# blinkm_mk2j.net
KiCad netlist of a schematic drawn in EAGLE
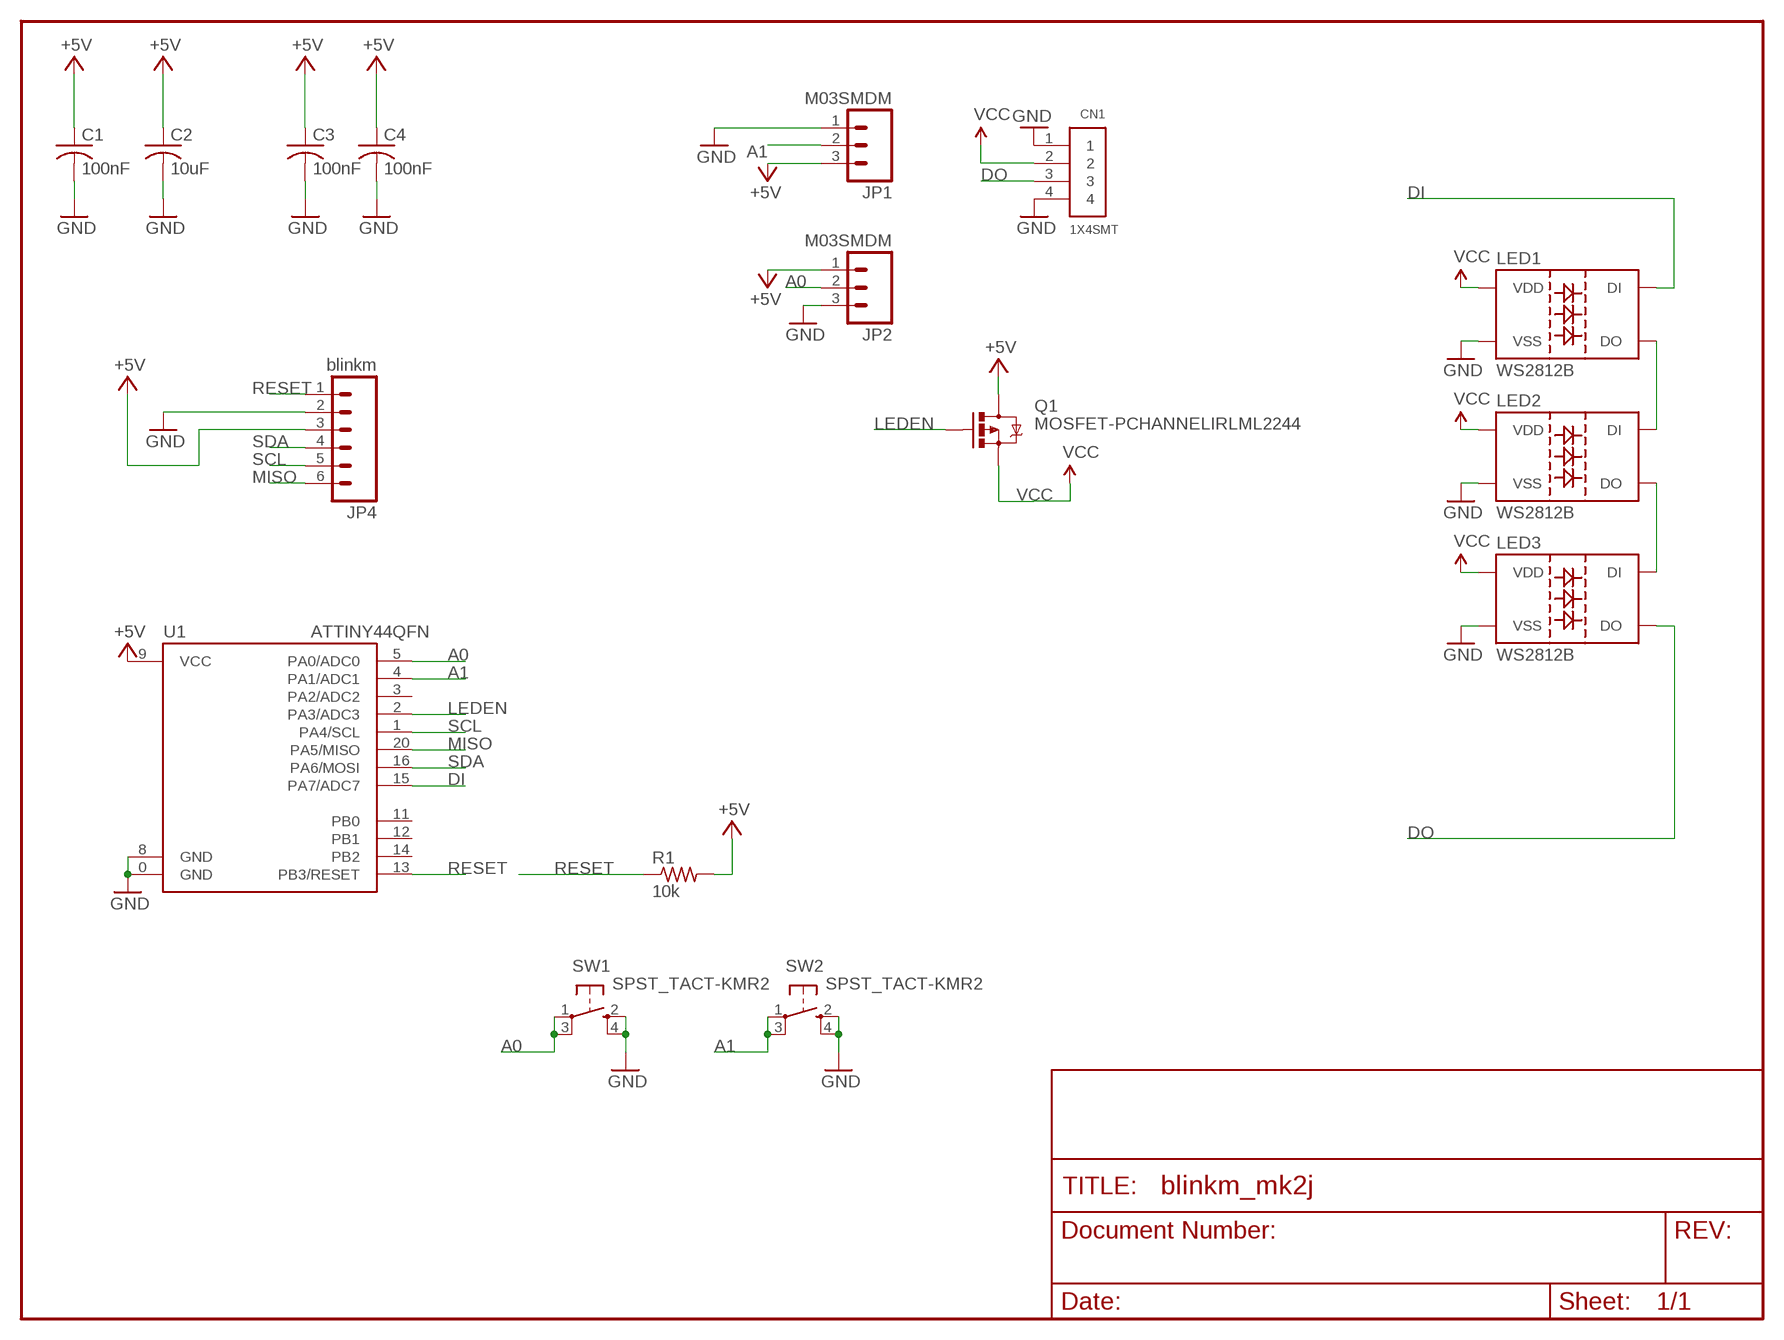
[diagram p0: schematic, sheet 1]

(export (version "E")
  (design (tool "Eeschema 10.0.6"))
  (components
    (comp (ref "C1")
      (value "100nF")
      (footprint "eagle-import:C0603")
      (libsource (lib "eagle-import") (part "C-USC0603"))
    )
    (comp (ref "C2")
      (value "10uF")
      (footprint "eagle-import:C0603")
      (libsource (lib "eagle-import") (part "C-USC0603"))
    )
    (comp (ref "C3")
      (value "100nF")
      (footprint "eagle-import:C0603")
      (libsource (lib "eagle-import") (part "C-USC0603"))
    )
    (comp (ref "C4")
      (value "100nF")
      (footprint "eagle-import:C0603")
      (libsource (lib "eagle-import") (part "C-USC0603"))
    )
    (comp (ref "CN1")
      (value "1X4SMT")
      (footprint "eagle-import:1X4-SMT")
      (libsource (lib "eagle-import") (part "1X4SMT"))
    )
    (comp (ref "JP1")
      (value "M03SMDM")
      (footprint "eagle-import:1X03-SMD-MINIMAL")
      (libsource (lib "eagle-import") (part "M03SMDM"))
    )
    (comp (ref "JP2")
      (value "M03SMDM")
      (footprint "eagle-import:1X03-SMD-MINIMAL")
      (libsource (lib "eagle-import") (part "M03SMDM"))
    )
    (comp (ref "JP4")
      (value "blinkm")
      (footprint "eagle-import:1X06_LOCK")
      (libsource (lib "eagle-import") (part "M06LOCK"))
    )
    (comp (ref "LED1")
      (value "WS2812B")
      (footprint "eagle-import:WS2812B")
      (libsource (lib "eagle-import") (part "WS2812B"))
    )
    (comp (ref "LED2")
      (value "WS2812B")
      (footprint "eagle-import:WS2812B")
      (libsource (lib "eagle-import") (part "WS2812B"))
    )
    (comp (ref "LED3")
      (value "WS2812B")
      (footprint "eagle-import:WS2812B")
      (libsource (lib "eagle-import") (part "WS2812B"))
    )
    (comp (ref "Q1")
      (value "MOSFET-PCHANNELIRLML2244")
      (footprint "eagle-import:SOT23-3")
      (libsource (lib "eagle-import") (part "MOSFET-PCHANNELIRLML2244"))
    )
    (comp (ref "R1")
      (value "10k")
      (footprint "eagle-import:R0603")
      (libsource (lib "eagle-import") (part "R-US_R0603"))
    )
    (comp (ref "SW1")
      (value "SPST_TACT-KMR2")
      (footprint "eagle-import:KMR2")
      (libsource (lib "eagle-import") (part "SPST_TACT-KMR2"))
    )
    (comp (ref "SW2")
      (value "SPST_TACT-KMR2")
      (footprint "eagle-import:KMR2")
      (libsource (lib "eagle-import") (part "SPST_TACT-KMR2"))
    )
    (comp (ref "U1")
      (value "ATTINY44QFN")
      (footprint "eagle-import:QFN20")
      (libsource (lib "eagle-import") (part "ATTINY24QFN"))
    )
  )
  (nets
    (net (code "1") (name "+5V") (class "Default")
      (node (ref "C1") (pin "1") (pinfunction "1_1") (pintype "passive"))
      (node (ref "C2") (pin "1") (pinfunction "1_1") (pintype "passive"))
      (node (ref "C3") (pin "1") (pinfunction "1_1") (pintype "passive"))
      (node (ref "C4") (pin "1") (pinfunction "1_1") (pintype "passive"))
      (node (ref "JP1") (pin "3") (pinfunction "3_3") (pintype "passive"))
      (node (ref "JP2") (pin "1") (pinfunction "1_1") (pintype "passive"))
      (node (ref "JP4") (pin "3") (pinfunction "3_3") (pintype "passive"))
      (node (ref "Q1") (pin "3") (pinfunction "D_3") (pintype "passive"))
      (node (ref "R1") (pin "2") (pinfunction "2_2") (pintype "passive"))
      (node (ref "U1") (pin "9") (pinfunction "VCC_9") (pintype "bidirectional"))
    )
    (net (code "2") (name "/A0") (class "Default")
      (node (ref "JP2") (pin "2") (pinfunction "2_2") (pintype "passive"))
      (node (ref "SW1") (pin "1") (pinfunction "P_1") (pintype "passive"))
      (node (ref "SW1") (pin "3") (pinfunction "P1_3") (pintype "passive"))
      (node (ref "U1") (pin "5") (pinfunction "PA0/ADC0_5") (pintype "bidirectional"))
    )
    (net (code "3") (name "/A1") (class "Default")
      (node (ref "JP1") (pin "2") (pinfunction "2_2") (pintype "passive"))
      (node (ref "SW2") (pin "1") (pinfunction "P_1") (pintype "passive"))
      (node (ref "SW2") (pin "3") (pinfunction "P1_3") (pintype "passive"))
      (node (ref "U1") (pin "4") (pinfunction "PA1/ADC1_4") (pintype "bidirectional"))
    )
    (net (code "4") (name "/DI") (class "Default")
      (node (ref "LED1") (pin "4") (pinfunction "DI_4") (pintype "bidirectional"))
      (node (ref "U1") (pin "15") (pinfunction "PA7/ADC7_15") (pintype "bidirectional"))
    )
    (net (code "5") (name "/DO") (class "Default")
      (node (ref "CN1") (pin "3") (pinfunction "3_3") (pintype "bidirectional"))
      (node (ref "LED3") (pin "2") (pinfunction "DO_2") (pintype "bidirectional"))
    )
    (net (code "6") (name "/LEDEN") (class "Default")
      (node (ref "Q1") (pin "1") (pinfunction "G_1") (pintype "passive"))
      (node (ref "U1") (pin "2") (pinfunction "PA3/ADC3_2") (pintype "bidirectional"))
    )
    (net (code "7") (name "/MISO") (class "Default")
      (node (ref "JP4") (pin "6") (pinfunction "6_6") (pintype "passive"))
      (node (ref "U1") (pin "20") (pinfunction "PA5/MISO_20") (pintype "bidirectional"))
    )
    (net (code "8") (name "/RESET") (class "Default")
      (node (ref "JP4") (pin "1") (pinfunction "1_1") (pintype "passive"))
      (node (ref "R1") (pin "1") (pinfunction "1_1") (pintype "passive"))
      (node (ref "U1") (pin "13") (pinfunction "PB3/RESET_13") (pintype "bidirectional"))
    )
    (net (code "9") (name "/SCL") (class "Default")
      (node (ref "JP4") (pin "5") (pinfunction "5_5") (pintype "passive"))
      (node (ref "U1") (pin "1") (pinfunction "PA4/SCL_1") (pintype "bidirectional"))
    )
    (net (code "10") (name "/SDA") (class "Default")
      (node (ref "JP4") (pin "4") (pinfunction "4_4") (pintype "passive"))
      (node (ref "U1") (pin "16") (pinfunction "PA6/MOSI_16") (pintype "bidirectional"))
    )
    (net (code "11") (name "GND") (class "Default")
      (node (ref "C1") (pin "2") (pinfunction "2_2") (pintype "passive"))
      (node (ref "C2") (pin "2") (pinfunction "2_2") (pintype "passive"))
      (node (ref "C3") (pin "2") (pinfunction "2_2") (pintype "passive"))
      (node (ref "C4") (pin "2") (pinfunction "2_2") (pintype "passive"))
      (node (ref "CN1") (pin "1") (pinfunction "1_1") (pintype "bidirectional"))
      (node (ref "CN1") (pin "4") (pinfunction "4_4") (pintype "bidirectional"))
      (node (ref "JP1") (pin "1") (pinfunction "1_1") (pintype "passive"))
      (node (ref "JP2") (pin "3") (pinfunction "3_3") (pintype "passive"))
      (node (ref "JP4") (pin "2") (pinfunction "2_2") (pintype "passive"))
      (node (ref "LED1") (pin "3") (pinfunction "VSS_3") (pintype "bidirectional"))
      (node (ref "LED2") (pin "3") (pinfunction "VSS_3") (pintype "bidirectional"))
      (node (ref "LED3") (pin "3") (pinfunction "VSS_3") (pintype "bidirectional"))
      (node (ref "SW1") (pin "2") (pinfunction "S_2") (pintype "passive"))
      (node (ref "SW1") (pin "4") (pinfunction "S1_4") (pintype "passive"))
      (node (ref "SW2") (pin "2") (pinfunction "S_2") (pintype "passive"))
      (node (ref "SW2") (pin "4") (pinfunction "S1_4") (pintype "passive"))
      (node (ref "U1") (pin "0") (pinfunction "GND_0") (pintype "bidirectional"))
      (node (ref "U1") (pin "8") (pinfunction "GND_8") (pintype "bidirectional"))
    )
    (net (code "12") (name "Net-(LED1-DO)") (class "Default")
      (node (ref "LED1") (pin "2") (pinfunction "DO_2") (pintype "bidirectional"))
      (node (ref "LED2") (pin "4") (pinfunction "DI_4") (pintype "bidirectional"))
    )
    (net (code "13") (name "Net-(LED2-DO)") (class "Default")
      (node (ref "LED2") (pin "2") (pinfunction "DO_2") (pintype "bidirectional"))
      (node (ref "LED3") (pin "4") (pinfunction "DI_4") (pintype "bidirectional"))
    )
    (net (code "14") (name "VCC") (class "Default")
      (node (ref "CN1") (pin "2") (pinfunction "2_2") (pintype "bidirectional"))
      (node (ref "LED1") (pin "1") (pinfunction "VDD_1") (pintype "bidirectional"))
      (node (ref "LED2") (pin "1") (pinfunction "VDD_1") (pintype "bidirectional"))
      (node (ref "LED3") (pin "1") (pinfunction "VDD_1") (pintype "bidirectional"))
      (node (ref "Q1") (pin "2") (pinfunction "S_2") (pintype "passive"))
    )
    (net (code "15") (name "unconnected-(U1-PA2{slash}ADC2-Pad3)") (class "Default")
      (node (ref "U1") (pin "3") (pinfunction "PA2/ADC2_3") (pintype "bidirectional"))
    )
    (net (code "16") (name "unconnected-(U1-PB0-Pad11)") (class "Default")
      (node (ref "U1") (pin "11") (pinfunction "PB0_11") (pintype "bidirectional"))
    )
    (net (code "17") (name "unconnected-(U1-PB1-Pad12)") (class "Default")
      (node (ref "U1") (pin "12") (pinfunction "PB1_12") (pintype "bidirectional"))
    )
    (net (code "18") (name "unconnected-(U1-PB2-Pad14)") (class "Default")
      (node (ref "U1") (pin "14") (pinfunction "PB2_14") (pintype "bidirectional"))
    )
  )
)
